# 0006_h_field_probe_15mm.net
KiCad netlist of a schematic drawn in EAGLE
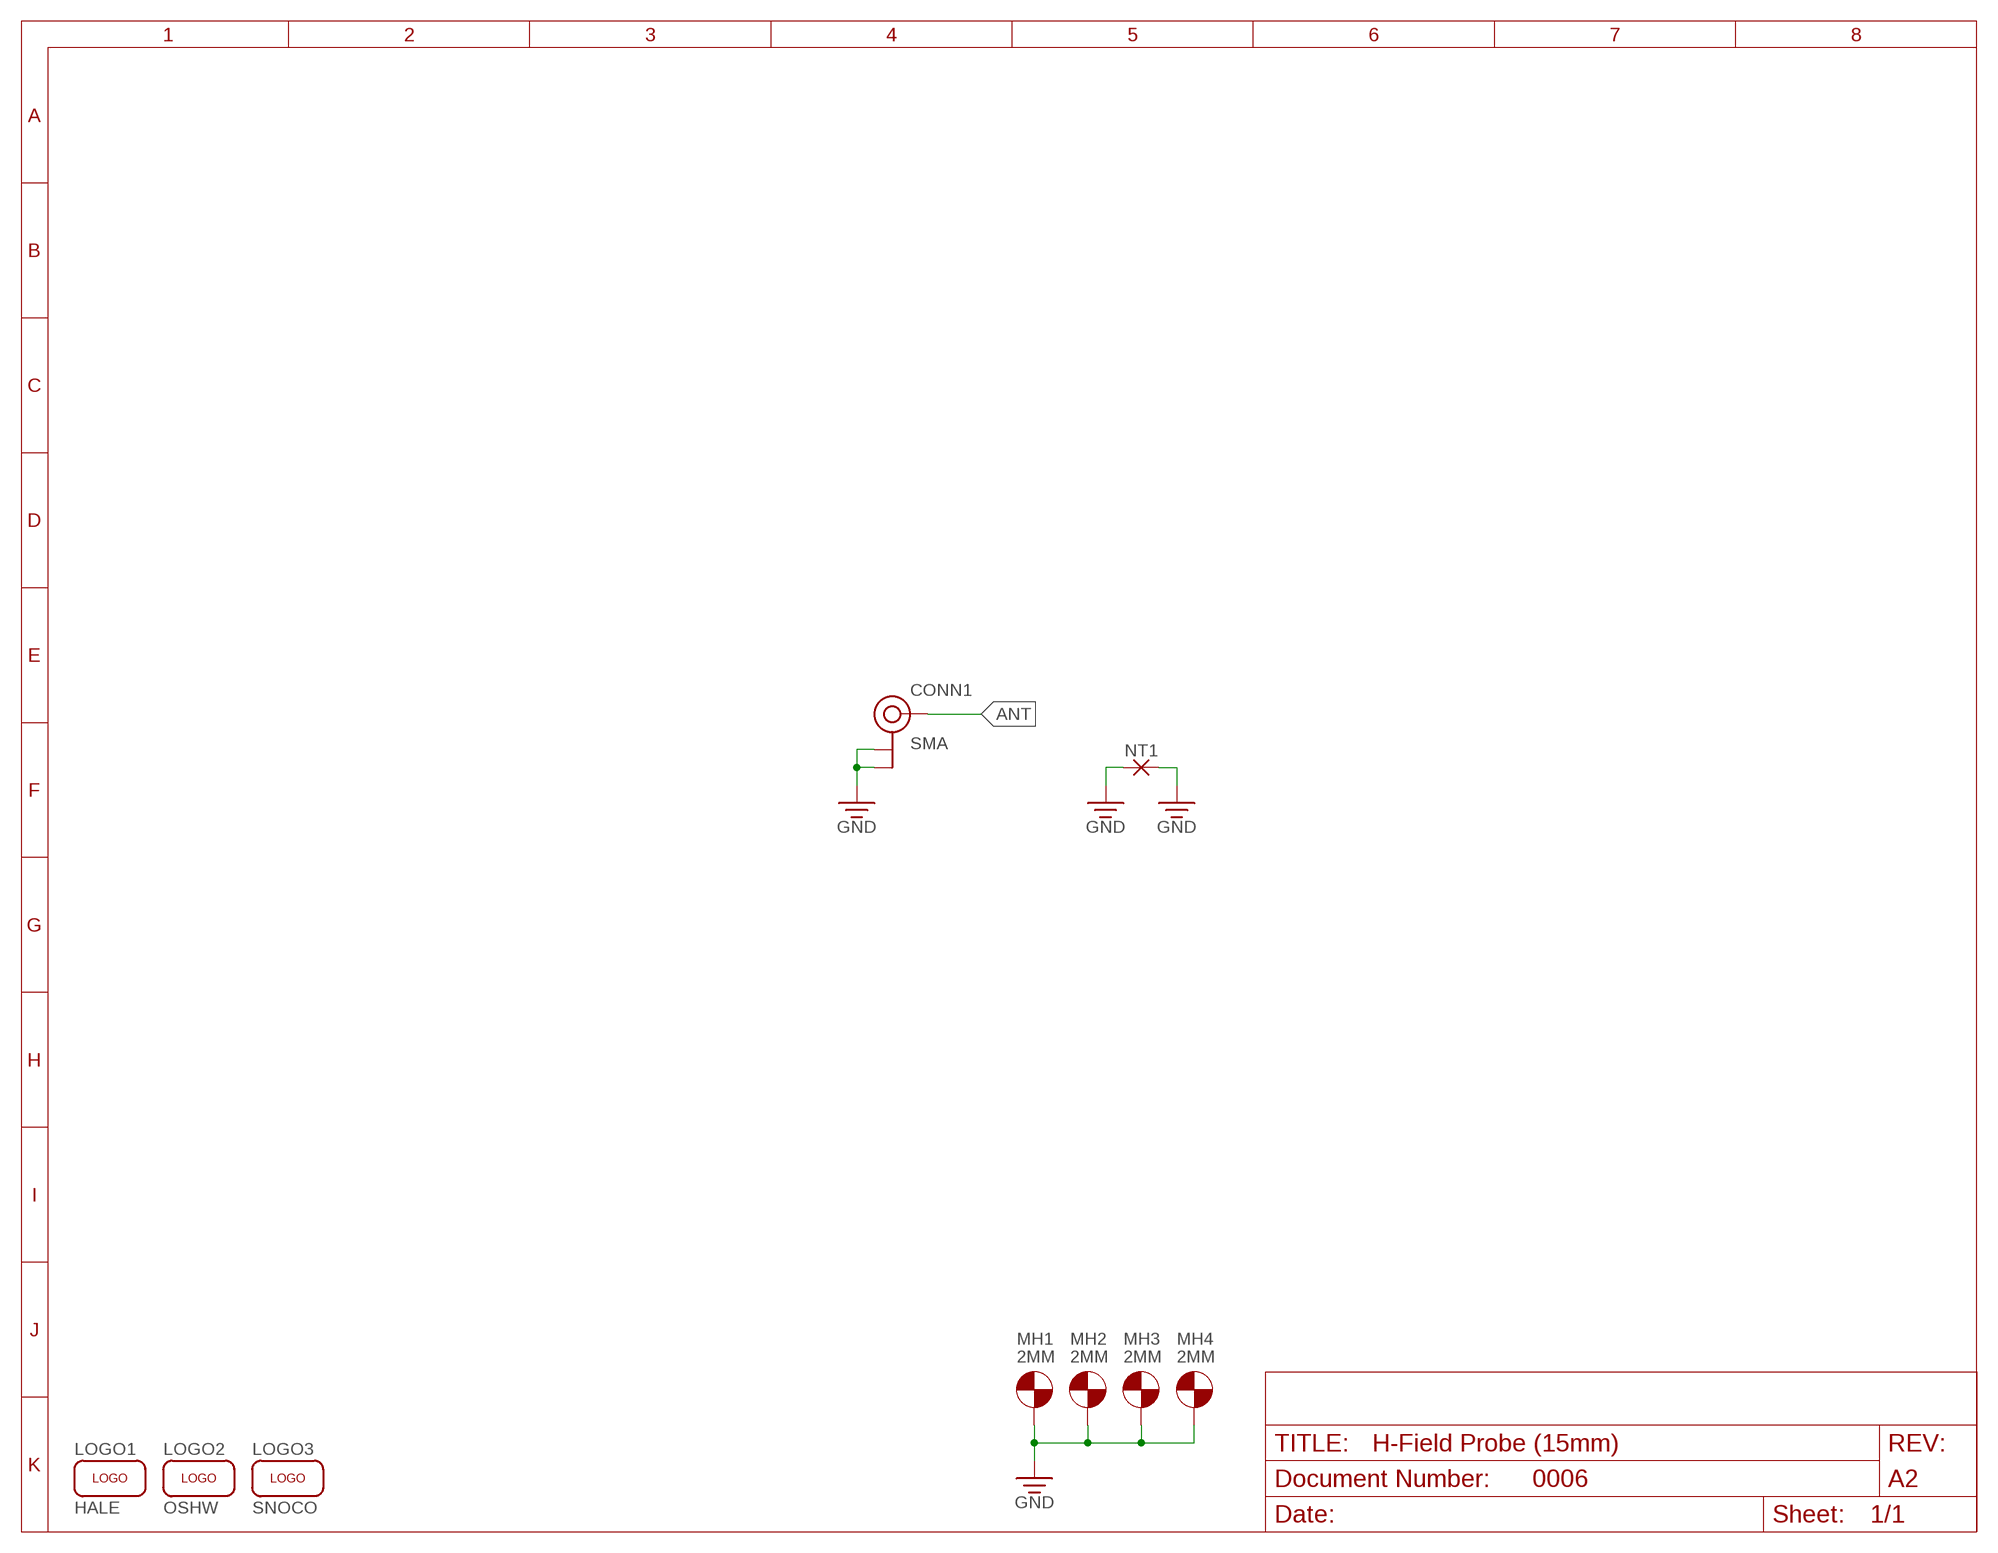
[diagram p0: schematic, sheet 1]

(export (version "E")
  (design (tool "Eeschema 10.0.6"))
  (components
    (comp (ref "CONN1")
      (value "SMA")
      (footprint "eagle-import:SMA-EDGE-6.5MM")
      (libsource (lib "eagle-import") (part "COAX-CONNECTOR-EDGE-SMA-6.5MM"))
    )
    (comp (ref "LOGO1")
      (value "HALE")
      (footprint "eagle-import:HALE-SILK-ICON")
      (libsource (lib "eagle-import") (part "LOGO-HALE"))
    )
    (comp (ref "LOGO2")
      (value "OSHW")
      (footprint "eagle-import:OSHW-SILK-ICON")
      (libsource (lib "eagle-import") (part "LOGO-OSHW"))
    )
    (comp (ref "LOGO3")
      (value "SNOCO")
      (footprint "eagle-import:SNOCO-SILK-ICON")
      (libsource (lib "eagle-import") (part "LOGO-SNOCO"))
    )
    (comp (ref "MH1")
      (value "2MM")
      (footprint "eagle-import:MH-M2-ELEC")
      (libsource (lib "eagle-import") (part "MH-ELEC-M2"))
    )
    (comp (ref "MH2")
      (value "2MM")
      (footprint "eagle-import:MH-M2-ELEC")
      (libsource (lib "eagle-import") (part "MH-ELEC-M2"))
    )
    (comp (ref "MH3")
      (value "2MM")
      (footprint "eagle-import:MH-M2-ELEC")
      (libsource (lib "eagle-import") (part "MH-ELEC-M2"))
    )
    (comp (ref "MH4")
      (value "2MM")
      (footprint "eagle-import:MH-M2-ELEC")
      (libsource (lib "eagle-import") (part "MH-ELEC-M2"))
    )
    (comp (ref "NT1")
      (value "NETTIE-VIA-TB")
      (footprint "eagle-import:NETTIE-VIA-TB")
      (libsource (lib "eagle-import") (part "NETTIE-VIA-TB"))
    )
    (comp (ref "U$2")
      (value "FRAME-8.5X11-LANDSCAPE-LET")
      (footprint "eagle-import:FRAME-8.5X11-LANDSCAPE")
      (fields
        (field (name "DOCNUM") "0006")
        (field (name "REV") "A2")
        (field (name "TITLE") "H-Field Probe (15mm)")
      )
      (libsource (lib "eagle-import") (part "FRAME-8.5X11-LANDSCAPE-LET"))
    )
  )
  (nets
    (net (code "1") (name "ANT") (class "Default")
      (node (ref "CONN1") (pin "2") (pinfunction "SIGNAL_2") (pintype "passive"))
    )
    (net (code "2") (name "GND") (class "Default")
      (node (ref "CONN1") (pin "1") (pinfunction "GND_1") (pintype "power_in"))
      (node (ref "CONN1") (pin "3") (pinfunction "GND_3") (pintype "power_in"))
      (node (ref "CONN1") (pin "4") (pinfunction "GND_4") (pintype "power_in"))
      (node (ref "CONN1") (pin "5") (pinfunction "GND_5") (pintype "power_in"))
      (node (ref "MH1") (pin "1") (pinfunction "1_1") (pintype "passive"))
      (node (ref "MH2") (pin "1") (pinfunction "1_1") (pintype "passive"))
      (node (ref "MH3") (pin "1") (pinfunction "1_1") (pintype "passive"))
      (node (ref "MH4") (pin "1") (pinfunction "1_1") (pintype "passive"))
      (node (ref "NT1") (pin "1") (pinfunction "1_1") (pintype "passive"))
      (node (ref "NT1") (pin "2") (pinfunction "2_2") (pintype "passive"))
    )
  )
)
